# main_stm.net
KiCad netlist of a schematic drawn in EAGLE
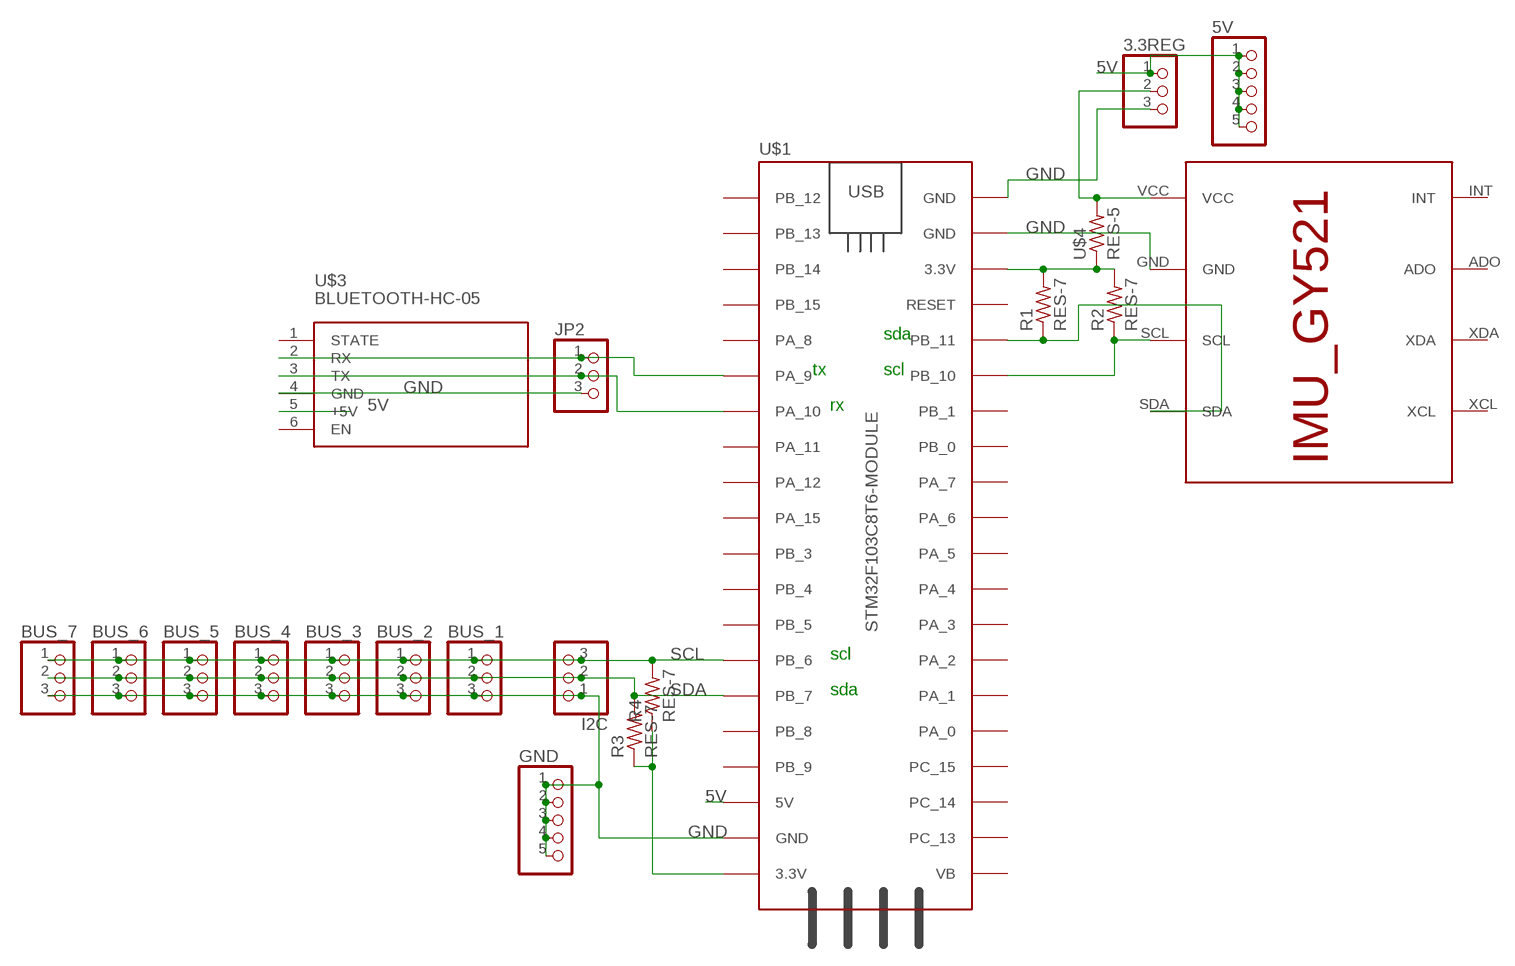
[diagram p0: schematic, sheet 1]

(export (version "E")
  (design (tool "Eeschema 10.0.6"))
  (components
    (comp (ref "3.3REG")
      (value "PINHD-1X3")
      (footprint "eagle-import:1X03")
      (libsource (lib "eagle-import") (part "PINHD-1X3"))
    )
    (comp (ref "5V")
      (value "PINHD-1X5")
      (footprint "eagle-import:1X05")
      (libsource (lib "eagle-import") (part "PINHD-1X5"))
    )
    (comp (ref "BUS_1")
      (value "PINHD-1X3")
      (footprint "eagle-import:1X03")
      (libsource (lib "eagle-import") (part "PINHD-1X3"))
    )
    (comp (ref "BUS_2")
      (value "PINHD-1X3")
      (footprint "eagle-import:1X03")
      (libsource (lib "eagle-import") (part "PINHD-1X3"))
    )
    (comp (ref "BUS_3")
      (value "PINHD-1X3")
      (footprint "eagle-import:1X03")
      (libsource (lib "eagle-import") (part "PINHD-1X3"))
    )
    (comp (ref "BUS_4")
      (value "PINHD-1X3")
      (footprint "eagle-import:1X03")
      (libsource (lib "eagle-import") (part "PINHD-1X3"))
    )
    (comp (ref "BUS_5")
      (value "PINHD-1X3")
      (footprint "eagle-import:1X03")
      (libsource (lib "eagle-import") (part "PINHD-1X3"))
    )
    (comp (ref "BUS_6")
      (value "PINHD-1X3")
      (footprint "eagle-import:1X03")
      (libsource (lib "eagle-import") (part "PINHD-1X3"))
    )
    (comp (ref "BUS_7")
      (value "PINHD-1X3")
      (footprint "eagle-import:1X03")
      (libsource (lib "eagle-import") (part "PINHD-1X3"))
    )
    (comp (ref "GND")
      (value "PINHD-1X5")
      (footprint "eagle-import:1X05")
      (libsource (lib "eagle-import") (part "PINHD-1X5"))
    )
    (comp (ref "I2C")
      (value "PINHD-1X3")
      (footprint "eagle-import:1X03")
      (libsource (lib "eagle-import") (part "PINHD-1X3"))
    )
    (comp (ref "JP2")
      (value "PINHD-1X3")
      (footprint "eagle-import:1X03")
      (libsource (lib "eagle-import") (part "PINHD-1X3"))
    )
    (comp (ref "R1")
      (value "RES-7")
      (footprint "eagle-import:0204_7")
      (libsource (lib "eagle-import") (part "RES-7"))
    )
    (comp (ref "R2")
      (value "RES-7")
      (footprint "eagle-import:0204_7")
      (libsource (lib "eagle-import") (part "RES-7"))
    )
    (comp (ref "R3")
      (value "RES-7")
      (footprint "eagle-import:0204_7")
      (libsource (lib "eagle-import") (part "RES-7"))
    )
    (comp (ref "R4")
      (value "RES-7")
      (footprint "eagle-import:0204_7")
      (libsource (lib "eagle-import") (part "RES-7"))
    )
    (comp (ref "U$1")
      (value "STM32F103C8T6-MODULE")
      (footprint "eagle-import:STM32F103C8T6-MODULE")
      (libsource (lib "eagle-import") (part "STM32F103C8T6-MODULE"))
    )
    (comp (ref "U$2")
      (value "IMU_ROBOCON_GY521")
      (footprint "eagle-import:IMU_GY521")
      (libsource (lib "eagle-import") (part "IMU_ROBOCON_GY521"))
    )
    (comp (ref "U$3")
      (value "BLUETOOTH-HC-05")
      (footprint "eagle-import:WIRELESS-BLUETOOTH-HC-05")
      (libsource (lib "eagle-import") (part "BLUETOOTH-HC-05"))
    )
    (comp (ref "U$4")
      (value "RES-5")
      (footprint "eagle-import:0204_5")
      (libsource (lib "eagle-import") (part "RES-5"))
    )
  )
  (nets
    (net (code "1") (name "/5V") (class "Default")
      (node (ref "3.3REG") (pin "1") (pinfunction "1_1") (pintype "passive"))
      (node (ref "5V") (pin "1") (pinfunction "1_1") (pintype "passive"))
      (node (ref "5V") (pin "2") (pinfunction "2_2") (pintype "passive"))
      (node (ref "5V") (pin "3") (pinfunction "3_3") (pintype "passive"))
      (node (ref "5V") (pin "4") (pinfunction "4_4") (pintype "passive"))
      (node (ref "5V") (pin "5") (pinfunction "5_5") (pintype "passive"))
      (node (ref "U$1") (pin "5V") (pinfunction "5V_5V") (pintype "bidirectional"))
      (node (ref "U$3") (pin "5") (pinfunction "+5V_5") (pintype "power_in"))
    )
    (net (code "2") (name "/GND") (class "Default")
      (node (ref "3.3REG") (pin "3") (pinfunction "3_3") (pintype "passive"))
      (node (ref "BUS_1") (pin "3") (pinfunction "3_3") (pintype "passive"))
      (node (ref "BUS_2") (pin "3") (pinfunction "3_3") (pintype "passive"))
      (node (ref "BUS_3") (pin "3") (pinfunction "3_3") (pintype "passive"))
      (node (ref "BUS_4") (pin "3") (pinfunction "3_3") (pintype "passive"))
      (node (ref "BUS_5") (pin "3") (pinfunction "3_3") (pintype "passive"))
      (node (ref "BUS_6") (pin "3") (pinfunction "3_3") (pintype "passive"))
      (node (ref "BUS_7") (pin "3") (pinfunction "3_3") (pintype "passive"))
      (node (ref "GND") (pin "1") (pinfunction "1_1") (pintype "passive"))
      (node (ref "GND") (pin "2") (pinfunction "2_2") (pintype "passive"))
      (node (ref "GND") (pin "3") (pinfunction "3_3") (pintype "passive"))
      (node (ref "GND") (pin "4") (pinfunction "4_4") (pintype "passive"))
      (node (ref "GND") (pin "5") (pinfunction "5_5") (pintype "passive"))
      (node (ref "I2C") (pin "1") (pinfunction "1_1") (pintype "passive"))
      (node (ref "JP2") (pin "3") (pinfunction "3_3") (pintype "passive"))
      (node (ref "U$1") (pin "GND_1") (pinfunction "GND_GND_1") (pintype "bidirectional"))
      (node (ref "U$1") (pin "GND_2") (pinfunction "GND_GND_2") (pintype "bidirectional"))
      (node (ref "U$1") (pin "GND_3") (pinfunction "GND_GND_3") (pintype "power_in"))
      (node (ref "U$2") (pin "GND") (pinfunction "GND_GND") (pintype "bidirectional"))
      (node (ref "U$3") (pin "4") (pinfunction "GND_4") (pintype "power_in"))
    )
    (net (code "3") (name "/SCL") (class "Default")
      (node (ref "BUS_1") (pin "1") (pinfunction "1_1") (pintype "passive"))
      (node (ref "BUS_2") (pin "1") (pinfunction "1_1") (pintype "passive"))
      (node (ref "BUS_3") (pin "1") (pinfunction "1_1") (pintype "passive"))
      (node (ref "BUS_4") (pin "1") (pinfunction "1_1") (pintype "passive"))
      (node (ref "BUS_5") (pin "1") (pinfunction "1_1") (pintype "passive"))
      (node (ref "BUS_6") (pin "1") (pinfunction "1_1") (pintype "passive"))
      (node (ref "BUS_7") (pin "1") (pinfunction "1_1") (pintype "passive"))
      (node (ref "I2C") (pin "3") (pinfunction "3_3") (pintype "passive"))
      (node (ref "R4") (pin "2") (pinfunction "2_2") (pintype "passive"))
      (node (ref "U$1") (pin "PB_6") (pinfunction "PB_6_PB_6") (pintype "bidirectional"))
    )
    (net (code "4") (name "/SDA") (class "Default")
      (node (ref "BUS_1") (pin "2") (pinfunction "2_2") (pintype "passive"))
      (node (ref "BUS_2") (pin "2") (pinfunction "2_2") (pintype "passive"))
      (node (ref "BUS_3") (pin "2") (pinfunction "2_2") (pintype "passive"))
      (node (ref "BUS_4") (pin "2") (pinfunction "2_2") (pintype "passive"))
      (node (ref "BUS_5") (pin "2") (pinfunction "2_2") (pintype "passive"))
      (node (ref "BUS_6") (pin "2") (pinfunction "2_2") (pintype "passive"))
      (node (ref "BUS_7") (pin "2") (pinfunction "2_2") (pintype "passive"))
      (node (ref "I2C") (pin "2") (pinfunction "2_2") (pintype "passive"))
      (node (ref "R3") (pin "2") (pinfunction "2_2") (pintype "passive"))
      (node (ref "U$1") (pin "PB_7") (pinfunction "PB_7_PB_7") (pintype "bidirectional"))
    )
    (net (code "5") (name "Net-(3.3REG-Pad2)") (class "Default")
      (node (ref "3.3REG") (pin "2") (pinfunction "2_2") (pintype "passive"))
      (node (ref "U$2") (pin "VCC") (pinfunction "VCC_VCC") (pintype "bidirectional"))
      (node (ref "U$4") (pin "2") (pinfunction "2_2") (pintype "passive"))
    )
    (net (code "6") (name "Net-(R1-Pad1)") (class "Default")
      (node (ref "R1") (pin "1") (pinfunction "1_1") (pintype "passive"))
      (node (ref "U$1") (pin "PB_11") (pinfunction "PB_11_PB_11") (pintype "bidirectional"))
      (node (ref "U$2") (pin "SDA") (pinfunction "SDA_SDA") (pintype "bidirectional"))
    )
    (net (code "7") (name "Net-(R1-Pad2)") (class "Default")
      (node (ref "R1") (pin "2") (pinfunction "2_2") (pintype "passive"))
      (node (ref "R2") (pin "2") (pinfunction "2_2") (pintype "passive"))
      (node (ref "U$1") (pin "3.3V_2") (pinfunction "3.3V_3.3V_2") (pintype "bidirectional"))
      (node (ref "U$4") (pin "1") (pinfunction "1_1") (pintype "passive"))
    )
    (net (code "8") (name "Net-(R2-Pad1)") (class "Default")
      (node (ref "R2") (pin "1") (pinfunction "1_1") (pintype "passive"))
      (node (ref "U$1") (pin "PB_10") (pinfunction "PB_10_PB_10") (pintype "bidirectional"))
      (node (ref "U$2") (pin "SCL") (pinfunction "SCL_SCL") (pintype "bidirectional"))
    )
    (net (code "9") (name "Net-(R3-Pad1)") (class "Default")
      (node (ref "R3") (pin "1") (pinfunction "1_1") (pintype "passive"))
      (node (ref "R4") (pin "1") (pinfunction "1_1") (pintype "passive"))
      (node (ref "U$1") (pin "3.3V_1") (pinfunction "3.3V_3.3V_1") (pintype "bidirectional"))
    )
    (net (code "10") (name "Net-(U$3-RX)") (class "Default")
      (node (ref "JP2") (pin "1") (pinfunction "1_1") (pintype "passive"))
      (node (ref "U$1") (pin "PA_9") (pinfunction "PA_9_PA_9") (pintype "bidirectional"))
      (node (ref "U$3") (pin "2") (pinfunction "RX_2") (pintype "bidirectional"))
    )
    (net (code "11") (name "Net-(U$3-TX)") (class "Default")
      (node (ref "JP2") (pin "2") (pinfunction "2_2") (pintype "passive"))
      (node (ref "U$1") (pin "PA_10") (pinfunction "PA_10_PA_10") (pintype "bidirectional"))
      (node (ref "U$3") (pin "3") (pinfunction "TX_3") (pintype "bidirectional"))
    )
    (net (code "12") (name "unconnected-(U$1-PadPA_0)") (class "Default")
      (node (ref "U$1") (pin "PA_0") (pinfunction "PA_0_PA_0") (pintype "bidirectional"))
    )
    (net (code "13") (name "unconnected-(U$1-PadPA_1)") (class "Default")
      (node (ref "U$1") (pin "PA_1") (pinfunction "PA_1_PA_1") (pintype "bidirectional"))
    )
    (net (code "14") (name "unconnected-(U$1-PadPA_2)") (class "Default")
      (node (ref "U$1") (pin "PA_2") (pinfunction "PA_2_PA_2") (pintype "bidirectional"))
    )
    (net (code "15") (name "unconnected-(U$1-PadPA_3)") (class "Default")
      (node (ref "U$1") (pin "PA_3") (pinfunction "PA_3_PA_3") (pintype "bidirectional"))
    )
    (net (code "16") (name "unconnected-(U$1-PadPA_4)") (class "Default")
      (node (ref "U$1") (pin "PA_4") (pinfunction "PA_4_PA_4") (pintype "bidirectional"))
    )
    (net (code "17") (name "unconnected-(U$1-PadPA_5)") (class "Default")
      (node (ref "U$1") (pin "PA_5") (pinfunction "PA_5_PA_5") (pintype "bidirectional"))
    )
    (net (code "18") (name "unconnected-(U$1-PadPA_6)") (class "Default")
      (node (ref "U$1") (pin "PA_6") (pinfunction "PA_6_PA_6") (pintype "bidirectional"))
    )
    (net (code "19") (name "unconnected-(U$1-PadPA_7)") (class "Default")
      (node (ref "U$1") (pin "PA_7") (pinfunction "PA_7_PA_7") (pintype "bidirectional"))
    )
    (net (code "20") (name "unconnected-(U$1-PadPA_8)") (class "Default")
      (node (ref "U$1") (pin "PA_8") (pinfunction "PA_8_PA_8") (pintype "bidirectional"))
    )
    (net (code "21") (name "unconnected-(U$1-PadPA_11)") (class "Default")
      (node (ref "U$1") (pin "PA_11") (pinfunction "PA_11_PA_11") (pintype "bidirectional"))
    )
    (net (code "22") (name "unconnected-(U$1-PadPA_12)") (class "Default")
      (node (ref "U$1") (pin "PA_12") (pinfunction "PA_12_PA_12") (pintype "bidirectional"))
    )
    (net (code "23") (name "unconnected-(U$1-PadPA_15)") (class "Default")
      (node (ref "U$1") (pin "PA_15") (pinfunction "PA_15_PA_15") (pintype "bidirectional"))
    )
    (net (code "24") (name "unconnected-(U$1-PadPB_0)") (class "Default")
      (node (ref "U$1") (pin "PB_0") (pinfunction "PB_0_PB_0") (pintype "bidirectional"))
    )
    (net (code "25") (name "unconnected-(U$1-PadPB_1)") (class "Default")
      (node (ref "U$1") (pin "PB_1") (pinfunction "PB_1_PB_1") (pintype "bidirectional"))
    )
    (net (code "26") (name "unconnected-(U$1-PadPB_3)") (class "Default")
      (node (ref "U$1") (pin "PB_3") (pinfunction "PB_3_PB_3") (pintype "bidirectional"))
    )
    (net (code "27") (name "unconnected-(U$1-PadPB_4)") (class "Default")
      (node (ref "U$1") (pin "PB_4") (pinfunction "PB_4_PB_4") (pintype "bidirectional"))
    )
    (net (code "28") (name "unconnected-(U$1-PadPB_5)") (class "Default")
      (node (ref "U$1") (pin "PB_5") (pinfunction "PB_5_PB_5") (pintype "bidirectional"))
    )
    (net (code "29") (name "unconnected-(U$1-PadPB_8)") (class "Default")
      (node (ref "U$1") (pin "PB_8") (pinfunction "PB_8_PB_8") (pintype "bidirectional"))
    )
    (net (code "30") (name "unconnected-(U$1-PadPB_9)") (class "Default")
      (node (ref "U$1") (pin "PB_9") (pinfunction "PB_9_PB_9") (pintype "bidirectional"))
    )
    (net (code "31") (name "unconnected-(U$1-PadPB_12)") (class "Default")
      (node (ref "U$1") (pin "PB_12") (pinfunction "PB_12_PB_12") (pintype "bidirectional"))
    )
    (net (code "32") (name "unconnected-(U$1-PadPB_13)") (class "Default")
      (node (ref "U$1") (pin "PB_13") (pinfunction "PB_13_PB_13") (pintype "bidirectional"))
    )
    (net (code "33") (name "unconnected-(U$1-PadPB_14)") (class "Default")
      (node (ref "U$1") (pin "PB_14") (pinfunction "PB_14_PB_14") (pintype "bidirectional"))
    )
    (net (code "34") (name "unconnected-(U$1-PadPB_15)") (class "Default")
      (node (ref "U$1") (pin "PB_15") (pinfunction "PB_15_PB_15") (pintype "bidirectional"))
    )
    (net (code "35") (name "unconnected-(U$1-PadPC_13)") (class "Default")
      (node (ref "U$1") (pin "PC_13") (pinfunction "PC_13_PC_13") (pintype "bidirectional"))
    )
    (net (code "36") (name "unconnected-(U$1-PadPC_14)") (class "Default")
      (node (ref "U$1") (pin "PC_14") (pinfunction "PC_14_PC_14") (pintype "bidirectional"))
    )
    (net (code "37") (name "unconnected-(U$1-PadPC_15)") (class "Default")
      (node (ref "U$1") (pin "PC_15") (pinfunction "PC_15_PC_15") (pintype "bidirectional"))
    )
    (net (code "38") (name "unconnected-(U$1-PadRESET)") (class "Default")
      (node (ref "U$1") (pin "RESET") (pinfunction "RESET_RESET") (pintype "bidirectional"))
    )
    (net (code "39") (name "unconnected-(U$1-PadVB)") (class "Default")
      (node (ref "U$1") (pin "VB") (pinfunction "VB_VB") (pintype "bidirectional"))
    )
    (net (code "40") (name "unconnected-(U$2-PadADO)") (class "Default")
      (node (ref "U$2") (pin "ADO") (pinfunction "ADO_ADO") (pintype "bidirectional"))
    )
    (net (code "41") (name "unconnected-(U$2-PadINT)") (class "Default")
      (node (ref "U$2") (pin "INT") (pinfunction "INT_INT") (pintype "bidirectional"))
    )
    (net (code "42") (name "unconnected-(U$2-PadXCL)") (class "Default")
      (node (ref "U$2") (pin "XCL") (pinfunction "XCL_XCL") (pintype "bidirectional"))
    )
    (net (code "43") (name "unconnected-(U$2-PadXDA)") (class "Default")
      (node (ref "U$2") (pin "XDA") (pinfunction "XDA_XDA") (pintype "bidirectional"))
    )
    (net (code "44") (name "unconnected-(U$3-EN-Pad6)") (class "Default")
      (node (ref "U$3") (pin "6") (pinfunction "EN_6") (pintype "bidirectional"))
    )
    (net (code "45") (name "unconnected-(U$3-STATE-Pad1)") (class "Default")
      (node (ref "U$3") (pin "1") (pinfunction "STATE_1") (pintype "bidirectional"))
    )
  )
)
